# Sheet1.net
KiCad netlist of a schematic drawn in Altium Designer
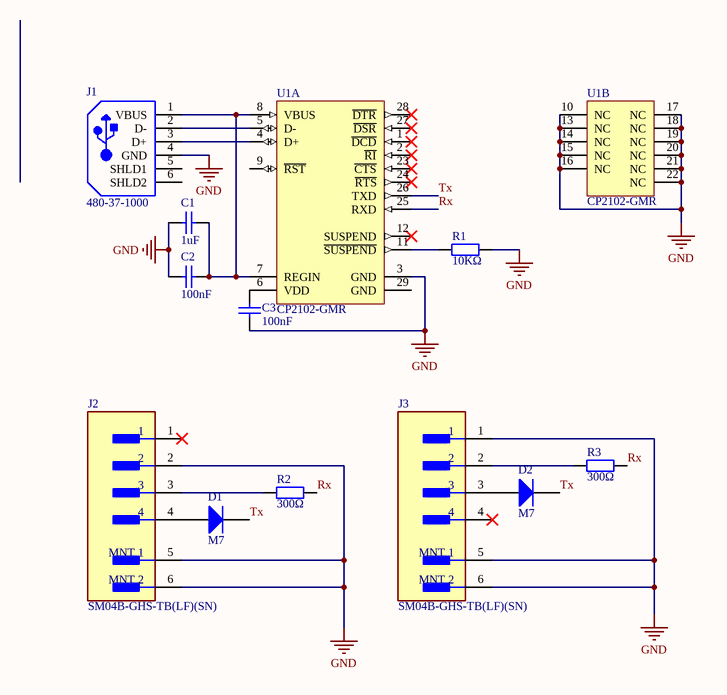
[diagram p0: Sheet1.SchDoc]

(export (version "E")
  (design (tool "Eeschema 10.0.6"))
  (components
    (comp (ref "C1")
      (value "1uF")
      (footprint "0603_C")
      (description "贴片电容, 1uF (105) 10% 50V")
      (libsource (lib "Miscellaneous Devices LC") (part "0603 1uF (105) 10% 50V"))
    )
    (comp (ref "C2")
      (value "100nF")
      (footprint "0402_C")
      (description "贴片电容, 100nF (104) 10% 16V")
      (libsource (lib "Miscellaneous Devices LC") (part "0402 100nF (104) 10% 16V"))
    )
    (comp (ref "C3")
      (value "100nF")
      (footprint "0402_C")
      (description "贴片电容, 100nF (104) 10% 16V")
      (libsource (lib "Miscellaneous Devices LC") (part "0402 100nF (104) 10% 16V"))
    )
    (comp (ref "D1")
      (value "M7")
      (footprint "SMA(DO-214AC)_S1")
      (description "二极管")
      (libsource (lib "Miscellaneous Devices LC") (part "SMA(DO-214AC) M7"))
    )
    (comp (ref "D2")
      (value "M7")
      (footprint "SMA(DO-214AC)_S1")
      (description "二极管")
      (libsource (lib "Miscellaneous Devices LC") (part "SMA(DO-214AC) M7"))
    )
    (comp (ref "J1")
      (value "480-37-1000")
      (footprint "MOLX-480-37-1000_V")
      (fields (field (name "TOLERANCE") "1%"))
      (libsource (lib "Altium Content Vault") (part "USB-4-2SHLD"))
    )
    (comp (ref "J2")
      (value "SM04B-GHS-TB(LF)(SN)")
      (footprint "FP-SM04B-GHS-TB_LF_SN-MFG")
      (description "CONN HEADER SMD R/A 4POS 1.25MM")
      (libsource (lib "Altium Content Vault") (part "f4320a1371cd6270e33bce1916c33c0"))
    )
    (comp (ref "J3")
      (value "SM04B-GHS-TB(LF)(SN)")
      (footprint "FP-SM04B-GHS-TB_LF_SN-MFG")
      (description "CONN HEADER SMD R/A 4POS 1.25MM")
      (libsource (lib "Altium Content Vault") (part "f4320a1371cd6270e33bce1916c33c0"))
    )
    (comp (ref "R1")
      (value "10KΩ")
      (footprint "0402_R")
      (description "贴片电阻, 10KΩ (1002) ±1%")
      (libsource (lib "Miscellaneous Devices LC") (part "0402 10KΩ (1002) 1%"))
    )
    (comp (ref "R2")
      (value "300Ω")
      (footprint "0402_R")
      (description "贴片电阻, 300Ω (3000) ±1%")
      (libsource (lib "Miscellaneous Devices LC") (part "0402 300Ω (3000) 1%"))
    )
    (comp (ref "R3")
      (value "300Ω")
      (footprint "0402_R")
      (description "贴片电阻, 300Ω (3000) ±1%")
      (libsource (lib "Miscellaneous Devices LC") (part "0402 300Ω (3000) 1%"))
    )
    (comp (ref "U1")
      (value "CP2102-GMR")
      (footprint "SLAB-QFN-28-3125x3125TP_M")
      (description "Single-Chip USB to URAT Bridge, 3.3 V, -40 to 85 degC, 28-Pin QFN, RoHS, Tape and Reel")
      (fields (field (name "MANUFACTURER") "Silicon Labs"))
      (libsource (lib "Altium Content Vault") (part "SLAB-CP210X-QFN-28-29"))
    )
  )
  (nets
    (net (code "1") (name "/Rx") (class "Default")
      (node (ref "R2") (pin "2") (pinfunction "2_2") (pintype "passive"))
      (node (ref "R3") (pin "2") (pinfunction "2_2") (pintype "passive"))
      (node (ref "U1") (pin "25") (pinfunction "RXD_25") (pintype "input"))
    )
    (net (code "2") (name "/Tx") (class "Default")
      (node (ref "D1") (pin "2") (pinfunction "K_2") (pintype "passive"))
      (node (ref "D2") (pin "2") (pinfunction "K_2") (pintype "passive"))
      (node (ref "U1") (pin "26") (pinfunction "TXD_26") (pintype "output"))
    )
    (net (code "3") (name "GND") (class "Default")
      (node (ref "C1") (pin "1") (pinfunction "1_1") (pintype "passive"))
      (node (ref "C2") (pin "1") (pinfunction "1_1") (pintype "passive"))
      (node (ref "C3") (pin "1") (pinfunction "1_1") (pintype "passive"))
      (node (ref "J1") (pin "4") (pinfunction "GND_4") (pintype "passive"))
      (node (ref "J2") (pin "2") (pinfunction "2_2") (pintype "passive"))
      (node (ref "J2") (pin "5") (pinfunction "MNT_1_5") (pintype "passive"))
      (node (ref "J2") (pin "6") (pinfunction "MNT_2_6") (pintype "passive"))
      (node (ref "J3") (pin "1") (pinfunction "1_1") (pintype "passive"))
      (node (ref "J3") (pin "5") (pinfunction "MNT_1_5") (pintype "passive"))
      (node (ref "J3") (pin "6") (pinfunction "MNT_2_6") (pintype "passive"))
      (node (ref "R1") (pin "2") (pinfunction "2_2") (pintype "passive"))
      (node (ref "U1") (pin "10") (pinfunction "NC_10") (pintype "passive"))
      (node (ref "U1") (pin "13") (pinfunction "NC_13") (pintype "passive"))
      (node (ref "U1") (pin "14") (pinfunction "NC_14") (pintype "passive"))
      (node (ref "U1") (pin "15") (pinfunction "NC_15") (pintype "passive"))
      (node (ref "U1") (pin "16") (pinfunction "NC_16") (pintype "passive"))
      (node (ref "U1") (pin "17") (pinfunction "NC_17") (pintype "passive"))
      (node (ref "U1") (pin "18") (pinfunction "NC_18") (pintype "passive"))
      (node (ref "U1") (pin "19") (pinfunction "NC_19") (pintype "passive"))
      (node (ref "U1") (pin "20") (pinfunction "NC_20") (pintype "passive"))
      (node (ref "U1") (pin "21") (pinfunction "NC_21") (pintype "passive"))
      (node (ref "U1") (pin "22") (pinfunction "NC_22") (pintype "passive"))
      (node (ref "U1") (pin "3") (pinfunction "GND_3") (pintype "power_in"))
    )
    (net (code "4") (name "Net-(D1-A)") (class "Default")
      (node (ref "D1") (pin "1") (pinfunction "A_1") (pintype "passive"))
      (node (ref "J2") (pin "4") (pinfunction "4_4") (pintype "passive"))
    )
    (net (code "5") (name "Net-(D2-A)") (class "Default")
      (node (ref "D2") (pin "1") (pinfunction "A_1") (pintype "passive"))
      (node (ref "J3") (pin "3") (pinfunction "3_3") (pintype "passive"))
    )
    (net (code "6") (name "Net-(J1-D+)") (class "Default")
      (node (ref "J1") (pin "3") (pinfunction "D+_3") (pintype "passive"))
      (node (ref "U1") (pin "4") (pinfunction "D+_4") (pintype "bidirectional"))
    )
    (net (code "7") (name "Net-(J1-D-)") (class "Default")
      (node (ref "J1") (pin "2") (pinfunction "D-_2") (pintype "passive"))
      (node (ref "U1") (pin "5") (pinfunction "D-_5") (pintype "bidirectional"))
    )
    (net (code "8") (name "Net-(J1-VBUS)") (class "Default")
      (node (ref "C1") (pin "2") (pinfunction "2_2") (pintype "passive"))
      (node (ref "C2") (pin "2") (pinfunction "2_2") (pintype "passive"))
      (node (ref "J1") (pin "1") (pinfunction "VBUS_1") (pintype "passive"))
      (node (ref "U1") (pin "7") (pinfunction "REGIN_7") (pintype "power_in"))
      (node (ref "U1") (pin "8") (pinfunction "VBUS_8") (pintype "input"))
    )
    (net (code "9") (name "Net-(J2-Pad3)") (class "Default")
      (node (ref "J2") (pin "3") (pinfunction "3_3") (pintype "passive"))
      (node (ref "R2") (pin "1") (pinfunction "1_1") (pintype "passive"))
    )
    (net (code "10") (name "Net-(J3-Pad2)") (class "Default")
      (node (ref "J3") (pin "2") (pinfunction "2_2") (pintype "passive"))
      (node (ref "R3") (pin "1") (pinfunction "1_1") (pintype "passive"))
    )
    (net (code "11") (name "Net-(U1A-VDD)") (class "Default")
      (node (ref "C3") (pin "2") (pinfunction "2_2") (pintype "passive"))
      (node (ref "U1") (pin "6") (pinfunction "VDD_6") (pintype "power_in"))
    )
    (net (code "12") (name "Net-(U1A-~{SUSPEND})") (class "Default")
      (node (ref "R1") (pin "1") (pinfunction "1_1") (pintype "passive"))
      (node (ref "U1") (pin "11") (pinfunction "~{SUSPEND}_11") (pintype "output"))
    )
    (net (code "13") (name "unconnected-(J1-SHLD1-Pad5)") (class "Default")
      (node (ref "J1") (pin "5") (pinfunction "SHLD1_5") (pintype "passive"))
    )
    (net (code "14") (name "unconnected-(J1-SHLD2-Pad6)") (class "Default")
      (node (ref "J1") (pin "6") (pinfunction "SHLD2_6") (pintype "passive"))
    )
    (net (code "15") (name "unconnected-(J2-Pad1)") (class "Default")
      (node (ref "J2") (pin "1") (pinfunction "1_1") (pintype "passive+no_connect"))
    )
    (net (code "16") (name "unconnected-(J3-Pad4)") (class "Default")
      (node (ref "J3") (pin "4") (pinfunction "4_4") (pintype "passive+no_connect"))
    )
    (net (code "17") (name "unconnected-(U1A-GND-Pad29)") (class "Default")
      (node (ref "U1") (pin "29") (pinfunction "GND_29") (pintype "power_in"))
    )
    (net (code "18") (name "unconnected-(U1A-SUSPEND-Pad12)") (class "Default")
      (node (ref "U1") (pin "12") (pinfunction "SUSPEND_12") (pintype "output+no_connect"))
    )
    (net (code "19") (name "unconnected-(U1A-~{CTS}-Pad23)") (class "Default")
      (node (ref "U1") (pin "23") (pinfunction "~{CTS}_23") (pintype "input+no_connect"))
    )
    (net (code "20") (name "unconnected-(U1A-~{DCD}-Pad1)") (class "Default")
      (node (ref "U1") (pin "1") (pinfunction "~{DCD}_1") (pintype "input+no_connect"))
    )
    (net (code "21") (name "unconnected-(U1A-~{DSR}-Pad27)") (class "Default")
      (node (ref "U1") (pin "27") (pinfunction "~{DSR}_27") (pintype "input+no_connect"))
    )
    (net (code "22") (name "unconnected-(U1A-~{DTR}-Pad28)") (class "Default")
      (node (ref "U1") (pin "28") (pinfunction "~{DTR}_28") (pintype "output+no_connect"))
    )
    (net (code "23") (name "unconnected-(U1A-~{RI}-Pad2)") (class "Default")
      (node (ref "U1") (pin "2") (pinfunction "~{RI}_2") (pintype "input+no_connect"))
    )
    (net (code "24") (name "unconnected-(U1A-~{RST}-Pad9)") (class "Default")
      (node (ref "U1") (pin "9") (pinfunction "~{RST}_9") (pintype "bidirectional"))
    )
    (net (code "25") (name "unconnected-(U1A-~{RTS}-Pad24)") (class "Default")
      (node (ref "U1") (pin "24") (pinfunction "~{RTS}_24") (pintype "output+no_connect"))
    )
  )
)
